# dram2.net
KiCad netlist of a schematic drawn in Altium Designer
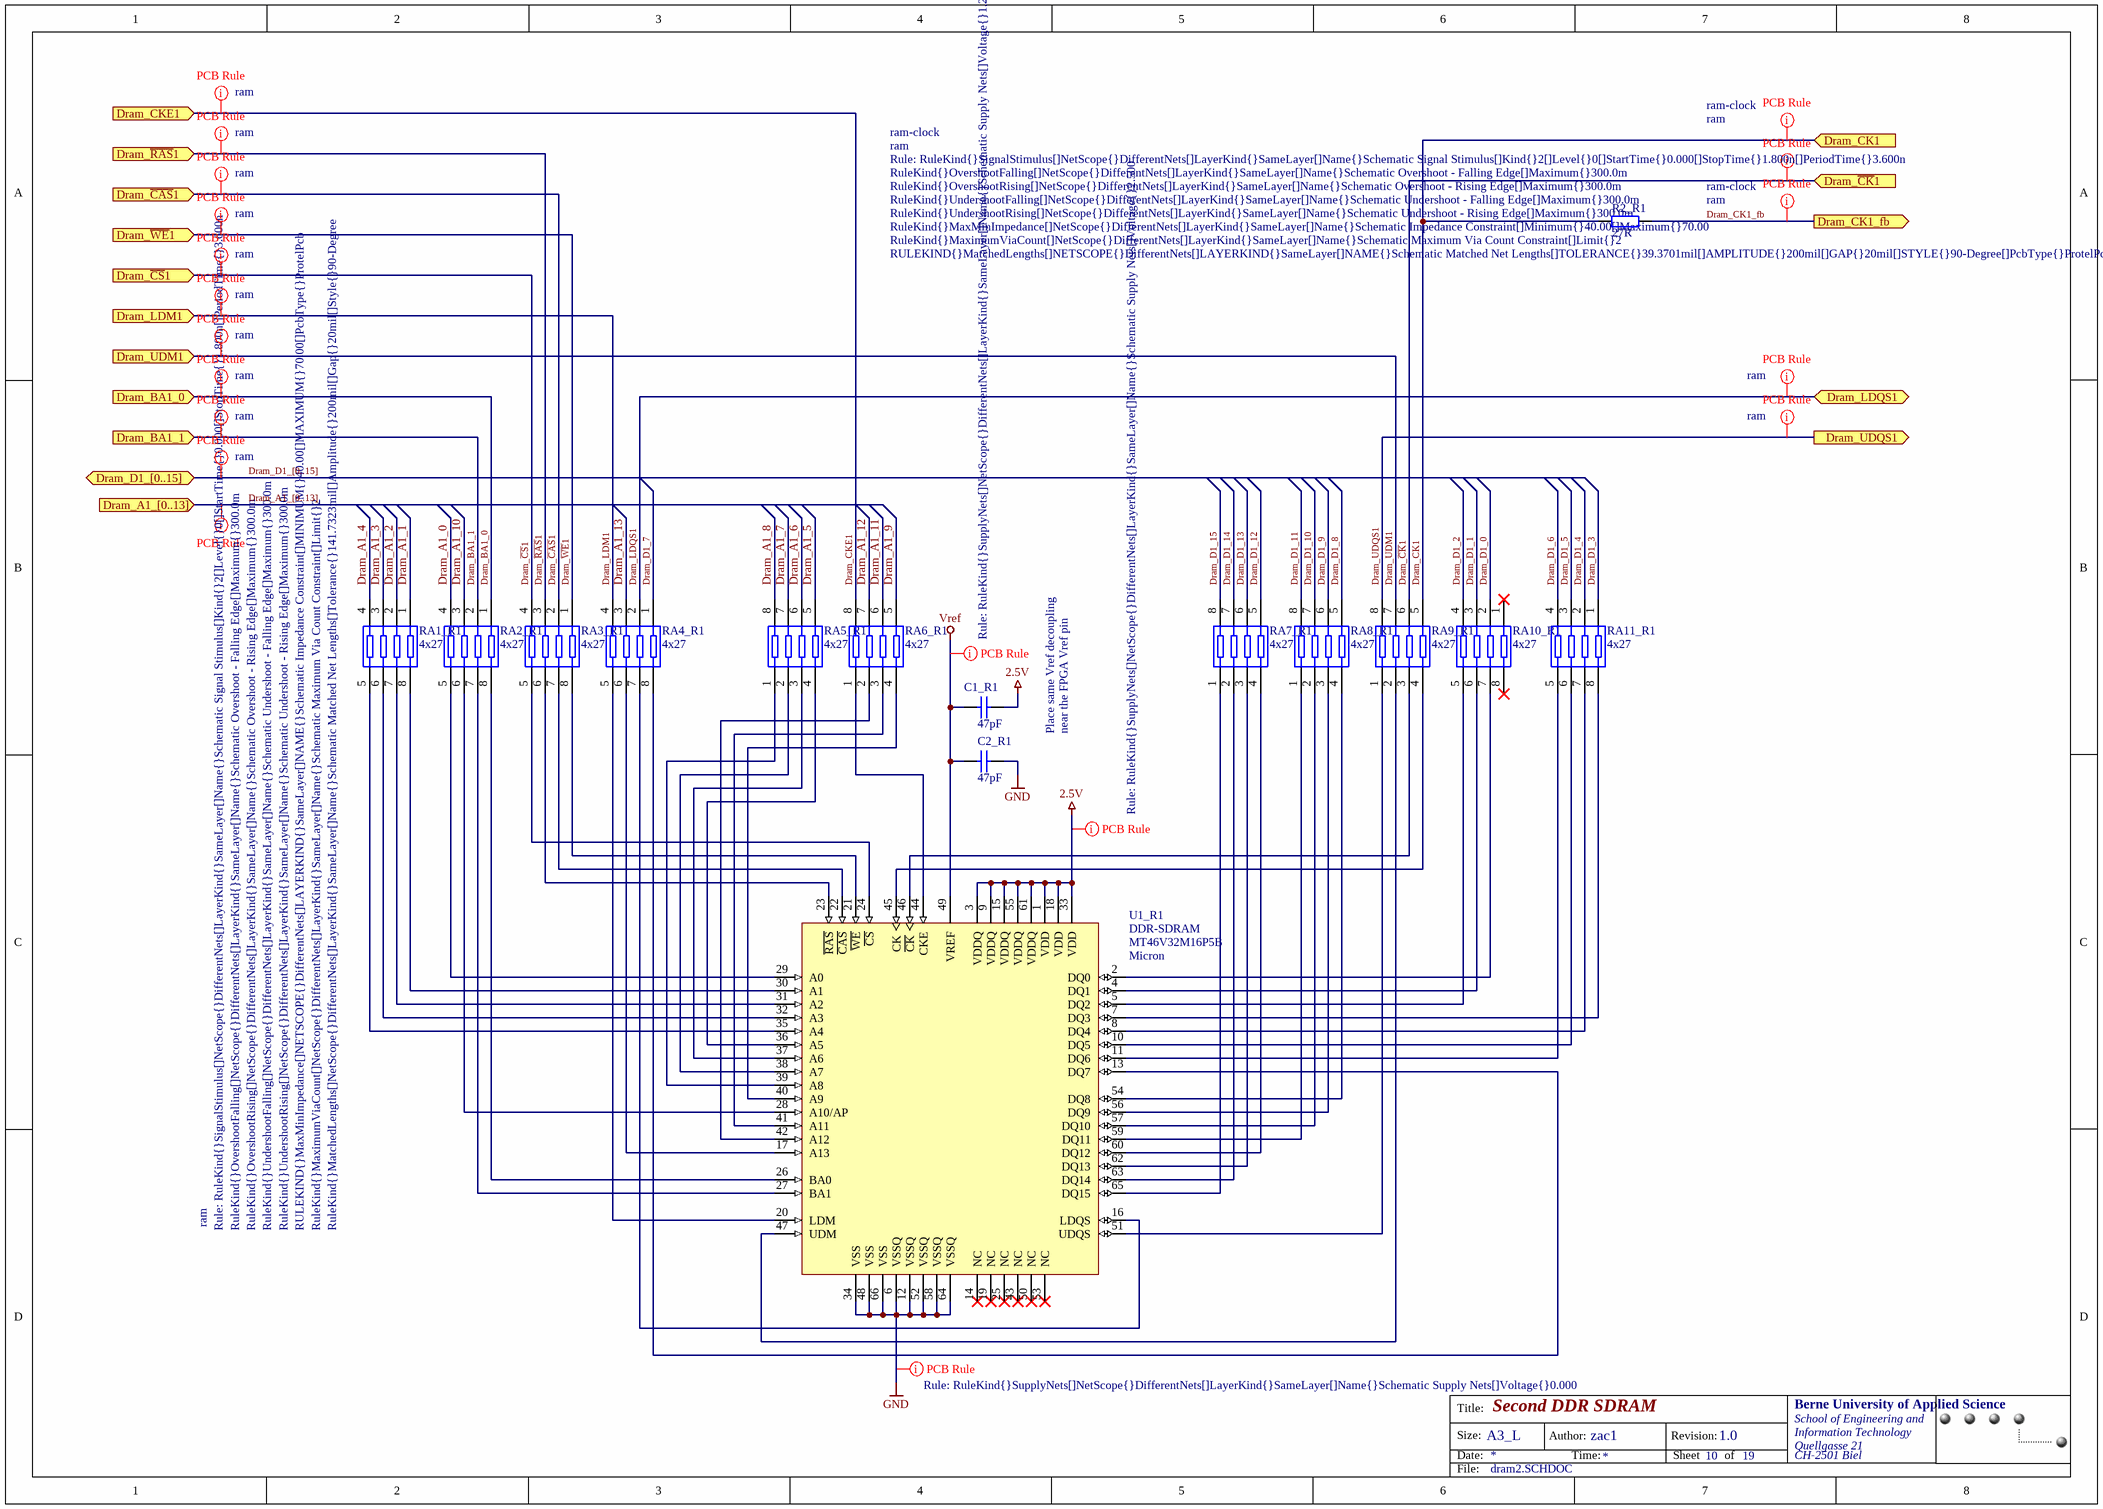
[diagram p0: dram2.SCHDOC]

(export (version "E")
  (design (tool "Eeschema 10.0.6"))
  (components
    (comp (ref "C1_R1")
      (value "47pF")
      (footprint "0402")
      (description "Capacitor")
      (fields
        (field (name "MANUFACTURER") "Murata")
        (field (name "PART NUMBER") "GRM1555C1H470JZ01D")
        (field (name "PUBLISHER") "Altium Limited")
      )
      (libsource (lib "Miscellaneous Devices") (part "Cap"))
    )
    (comp (ref "C2_R1")
      (value "47pF")
      (footprint "0402")
      (description "Capacitor")
      (fields
        (field (name "MANUFACTURER") "Murata")
        (field (name "PART NUMBER") "GRM1555C1H470JZ01D")
        (field (name "PUBLISHER") "Altium Limited")
      )
      (libsource (lib "Miscellaneous Devices") (part "Cap"))
    )
    (comp (ref "R2_R1")
      (value "27R")
      (footprint "0402")
      (description "Resistor")
      (fields
        (field (name "MANUFACTURER") "PHYCOMP")
        (field (name "PART NUMBER") "232270672709")
        (field (name "PUBLISHER") "Altium Limited")
      )
      (libsource (lib "Miscellaneous Devices") (part "Res2"))
    )
    (comp (ref "RA1_R1")
      (value "4x27")
      (footprint "1206_ARRAY")
      (fields (field (name "MANUFACTURER") "PHYCOMP") (field (name "PART NUMBER") "235003410279"))
      (libsource (lib "CoolARM-Kit") (part "R_ARRAY_4_SMD"))
    )
    (comp (ref "RA2_R1")
      (value "4x27")
      (footprint "1206_ARRAY")
      (fields (field (name "MANUFACTURER") "PHYCOMP") (field (name "PART NUMBER") "235003410279"))
      (libsource (lib "CoolARM-Kit") (part "R_ARRAY_4_SMD"))
    )
    (comp (ref "RA3_R1")
      (value "4x27")
      (footprint "1206_ARRAY")
      (fields (field (name "MANUFACTURER") "PHYCOMP") (field (name "PART NUMBER") "235003410279"))
      (libsource (lib "CoolARM-Kit") (part "R_ARRAY_4_SMD"))
    )
    (comp (ref "RA4_R1")
      (value "4x27")
      (footprint "1206_ARRAY")
      (fields (field (name "MANUFACTURER") "PHYCOMP") (field (name "PART NUMBER") "235003410279"))
      (libsource (lib "CoolARM-Kit") (part "R_ARRAY_4_SMD"))
    )
    (comp (ref "RA5_R1")
      (value "4x27")
      (footprint "1206_ARRAY")
      (fields (field (name "MANUFACTURER") "PHYCOMP") (field (name "PART NUMBER") "235003410279"))
      (libsource (lib "CoolARM-Kit") (part "R_ARRAY_4_SMD"))
    )
    (comp (ref "RA6_R1")
      (value "4x27")
      (footprint "1206_ARRAY")
      (fields (field (name "MANUFACTURER") "PHYCOMP") (field (name "PART NUMBER") "235003410279"))
      (libsource (lib "CoolARM-Kit") (part "R_ARRAY_4_SMD"))
    )
    (comp (ref "RA7_R1")
      (value "4x27")
      (footprint "1206_ARRAY")
      (fields (field (name "MANUFACTURER") "PHYCOMP") (field (name "PART NUMBER") "235003410279"))
      (libsource (lib "CoolARM-Kit") (part "R_ARRAY_4_SMD"))
    )
    (comp (ref "RA8_R1")
      (value "4x27")
      (footprint "1206_ARRAY")
      (fields (field (name "MANUFACTURER") "PHYCOMP") (field (name "PART NUMBER") "235003410279"))
      (libsource (lib "CoolARM-Kit") (part "R_ARRAY_4_SMD"))
    )
    (comp (ref "RA9_R1")
      (value "4x27")
      (footprint "1206_ARRAY")
      (fields (field (name "MANUFACTURER") "PHYCOMP") (field (name "PART NUMBER") "235003410279"))
      (libsource (lib "CoolARM-Kit") (part "R_ARRAY_4_SMD"))
    )
    (comp (ref "RA10_R1")
      (value "4x27")
      (footprint "1206_ARRAY")
      (fields (field (name "MANUFACTURER") "PHYCOMP") (field (name "PART NUMBER") "235003410279"))
      (libsource (lib "CoolARM-Kit") (part "R_ARRAY_4_SMD"))
    )
    (comp (ref "RA11_R1")
      (value "4x27")
      (footprint "1206_ARRAY")
      (fields (field (name "MANUFACTURER") "PHYCOMP") (field (name "PART NUMBER") "235003410279"))
      (libsource (lib "CoolARM-Kit") (part "R_ARRAY_4_SMD"))
    )
    (comp (ref "U1_R1")
      (value "DDR-SDRAM")
      (footprint "TSOP66")
      (description "general model for ddr sdram's")
      (fields
        (field (name "ALTIUM_VALUE") "MT46V32M16P5B")
        (field (name "VENDOR") "Micron")
        (field (name "MANUFACTURER") "Micron")
        (field (name "PART NUMBER") "MT46V32M16P5B")
      )
      (libsource (lib "gecko3-user") (part "DDR-SDRAM"))
    )
  )
  (nets
    (net (code "1") (name "/Dram_A1_0") (class "Default")
      (node (ref "RA2_R1") (pin "4") (pinfunction "4_4") (pintype "passive"))
    )
    (net (code "2") (name "/Dram_A1_1") (class "Default")
      (node (ref "RA1_R1") (pin "1") (pinfunction "1_1") (pintype "passive"))
    )
    (net (code "3") (name "/Dram_A1_2") (class "Default")
      (node (ref "RA1_R1") (pin "2") (pinfunction "2_2") (pintype "passive"))
    )
    (net (code "4") (name "/Dram_A1_3") (class "Default")
      (node (ref "RA1_R1") (pin "3") (pinfunction "3_3") (pintype "passive"))
    )
    (net (code "5") (name "/Dram_A1_4") (class "Default")
      (node (ref "RA1_R1") (pin "4") (pinfunction "4_4") (pintype "passive"))
    )
    (net (code "6") (name "/Dram_A1_5") (class "Default")
      (node (ref "RA5_R1") (pin "5") (pinfunction "5_5") (pintype "passive"))
    )
    (net (code "7") (name "/Dram_A1_6") (class "Default")
      (node (ref "RA5_R1") (pin "6") (pinfunction "6_6") (pintype "passive"))
    )
    (net (code "8") (name "/Dram_A1_7") (class "Default")
      (node (ref "RA5_R1") (pin "7") (pinfunction "7_7") (pintype "passive"))
    )
    (net (code "9") (name "/Dram_A1_8") (class "Default")
      (node (ref "RA5_R1") (pin "8") (pinfunction "8_8") (pintype "passive"))
    )
    (net (code "10") (name "/Dram_A1_9") (class "Default")
      (node (ref "RA6_R1") (pin "5") (pinfunction "5_5") (pintype "passive"))
    )
    (net (code "11") (name "/Dram_A1_10") (class "Default")
      (node (ref "RA2_R1") (pin "3") (pinfunction "3_3") (pintype "passive"))
    )
    (net (code "12") (name "/Dram_A1_11") (class "Default")
      (node (ref "RA6_R1") (pin "6") (pinfunction "6_6") (pintype "passive"))
    )
    (net (code "13") (name "/Dram_A1_12") (class "Default")
      (node (ref "RA6_R1") (pin "7") (pinfunction "7_7") (pintype "passive"))
    )
    (net (code "14") (name "/Dram_A1_13") (class "Default")
      (node (ref "RA4_R1") (pin "3") (pinfunction "3_3") (pintype "passive"))
    )
    (net (code "16") (name "/Dram_BA1_0") (class "Default")
      (node (ref "RA2_R1") (pin "1") (pinfunction "1_1") (pintype "passive"))
    )
    (net (code "17") (name "/Dram_BA1_1") (class "Default")
      (node (ref "RA2_R1") (pin "2") (pinfunction "2_2") (pintype "passive"))
    )
    (net (code "18") (name "/Dram_CK1") (class "Default")
      (node (ref "R2_R1") (pin "2") (pinfunction "2_2") (pintype "passive"))
      (node (ref "RA9_R1") (pin "5") (pinfunction "5_5") (pintype "passive"))
    )
    (net (code "19") (name "/Dram_CK1_fb") (class "Default")
      (node (ref "R2_R1") (pin "1") (pinfunction "1_1") (pintype "passive"))
    )
    (net (code "20") (name "/Dram_CKE1") (class "Default")
      (node (ref "RA6_R1") (pin "8") (pinfunction "8_8") (pintype "passive"))
    )
    (net (code "21") (name "/Dram_D1_0") (class "Default")
      (node (ref "RA10_R1") (pin "2") (pinfunction "2_2") (pintype "passive"))
    )
    (net (code "22") (name "/Dram_D1_1") (class "Default")
      (node (ref "RA10_R1") (pin "3") (pinfunction "3_3") (pintype "passive"))
    )
    (net (code "23") (name "/Dram_D1_2") (class "Default")
      (node (ref "RA10_R1") (pin "4") (pinfunction "4_4") (pintype "passive"))
    )
    (net (code "24") (name "/Dram_D1_3") (class "Default")
      (node (ref "RA11_R1") (pin "1") (pinfunction "1_1") (pintype "passive"))
    )
    (net (code "25") (name "/Dram_D1_4") (class "Default")
      (node (ref "RA11_R1") (pin "2") (pinfunction "2_2") (pintype "passive"))
    )
    (net (code "26") (name "/Dram_D1_5") (class "Default")
      (node (ref "RA11_R1") (pin "3") (pinfunction "3_3") (pintype "passive"))
    )
    (net (code "27") (name "/Dram_D1_6") (class "Default")
      (node (ref "RA11_R1") (pin "4") (pinfunction "4_4") (pintype "passive"))
    )
    (net (code "28") (name "/Dram_D1_7") (class "Default")
      (node (ref "RA4_R1") (pin "1") (pinfunction "1_1") (pintype "passive"))
    )
    (net (code "29") (name "/Dram_D1_8") (class "Default")
      (node (ref "RA8_R1") (pin "5") (pinfunction "5_5") (pintype "passive"))
    )
    (net (code "30") (name "/Dram_D1_9") (class "Default")
      (node (ref "RA8_R1") (pin "6") (pinfunction "6_6") (pintype "passive"))
    )
    (net (code "31") (name "/Dram_D1_10") (class "Default")
      (node (ref "RA8_R1") (pin "7") (pinfunction "7_7") (pintype "passive"))
    )
    (net (code "32") (name "/Dram_D1_11") (class "Default")
      (node (ref "RA8_R1") (pin "8") (pinfunction "8_8") (pintype "passive"))
    )
    (net (code "33") (name "/Dram_D1_12") (class "Default")
      (node (ref "RA7_R1") (pin "5") (pinfunction "5_5") (pintype "passive"))
    )
    (net (code "34") (name "/Dram_D1_13") (class "Default")
      (node (ref "RA7_R1") (pin "6") (pinfunction "6_6") (pintype "passive"))
    )
    (net (code "35") (name "/Dram_D1_14") (class "Default")
      (node (ref "RA7_R1") (pin "7") (pinfunction "7_7") (pintype "passive"))
    )
    (net (code "36") (name "/Dram_D1_15") (class "Default")
      (node (ref "RA7_R1") (pin "8") (pinfunction "8_8") (pintype "passive"))
    )
    (net (code "38") (name "/Dram_LDM1") (class "Default")
      (node (ref "RA4_R1") (pin "4") (pinfunction "4_4") (pintype "passive"))
    )
    (net (code "39") (name "/Dram_LDQS1") (class "Default")
      (node (ref "RA4_R1") (pin "2") (pinfunction "2_2") (pintype "passive"))
    )
    (net (code "40") (name "/Dram_UDM1") (class "Default")
      (node (ref "RA9_R1") (pin "7") (pinfunction "7_7") (pintype "passive"))
    )
    (net (code "41") (name "/Dram_UDQS1") (class "Default")
      (node (ref "RA9_R1") (pin "8") (pinfunction "8_8") (pintype "passive"))
    )
    (net (code "42") (name "/Dram_~{CAS}1") (class "Default")
      (node (ref "RA3_R1") (pin "2") (pinfunction "2_2") (pintype "passive"))
    )
    (net (code "43") (name "/Dram_~{CK}1") (class "Default")
      (node (ref "RA9_R1") (pin "6") (pinfunction "6_6") (pintype "passive"))
    )
    (net (code "44") (name "/Dram_~{CS}1") (class "Default")
      (node (ref "RA3_R1") (pin "4") (pinfunction "4_4") (pintype "passive"))
    )
    (net (code "45") (name "/Dram_~{RAS}1") (class "Default")
      (node (ref "RA3_R1") (pin "3") (pinfunction "3_3") (pintype "passive"))
    )
    (net (code "46") (name "/Dram_~{WE}1") (class "Default")
      (node (ref "RA3_R1") (pin "1") (pinfunction "1_1") (pintype "passive"))
    )
    (net (code "47") (name "2.5V") (class "Default")
      (node (ref "C1_R1") (pin "1") (pinfunction "1_1") (pintype "passive"))
      (node (ref "U1_R1") (pin "1") (pinfunction "VDD_1") (pintype "power_in"))
      (node (ref "U1_R1") (pin "15") (pinfunction "VDDQ_15") (pintype "power_in"))
      (node (ref "U1_R1") (pin "18") (pinfunction "VDD_18") (pintype "power_in"))
      (node (ref "U1_R1") (pin "3") (pinfunction "VDDQ_3") (pintype "power_in"))
      (node (ref "U1_R1") (pin "33") (pinfunction "VDD_33") (pintype "power_in"))
      (node (ref "U1_R1") (pin "55") (pinfunction "VDDQ_55") (pintype "power_in"))
      (node (ref "U1_R1") (pin "61") (pinfunction "VDDQ_61") (pintype "power_in"))
      (node (ref "U1_R1") (pin "9") (pinfunction "VDDQ_9") (pintype "power_in"))
    )
    (net (code "48") (name "GND") (class "Default")
      (node (ref "C2_R1") (pin "1") (pinfunction "1_1") (pintype "passive"))
      (node (ref "U1_R1") (pin "12") (pinfunction "VSSQ_12") (pintype "power_in"))
      (node (ref "U1_R1") (pin "34") (pinfunction "VSS_34") (pintype "power_in"))
      (node (ref "U1_R1") (pin "48") (pinfunction "VSS_48") (pintype "power_in"))
      (node (ref "U1_R1") (pin "52") (pinfunction "VSSQ_52") (pintype "power_in"))
      (node (ref "U1_R1") (pin "58") (pinfunction "VSSQ_58") (pintype "power_in"))
      (node (ref "U1_R1") (pin "6") (pinfunction "VSSQ_6") (pintype "power_in"))
      (node (ref "U1_R1") (pin "64") (pinfunction "VSSQ_64") (pintype "power_in"))
      (node (ref "U1_R1") (pin "66") (pinfunction "VSS_66") (pintype "power_in"))
    )
    (net (code "49") (name "Net-(U1_R1-A0)") (class "Default")
      (node (ref "RA2_R1") (pin "5") (pinfunction "5_5") (pintype "passive"))
      (node (ref "U1_R1") (pin "29") (pinfunction "A0_29") (pintype "input"))
    )
    (net (code "50") (name "Net-(U1_R1-A1)") (class "Default")
      (node (ref "RA1_R1") (pin "8") (pinfunction "8_8") (pintype "passive"))
      (node (ref "U1_R1") (pin "30") (pinfunction "A1_30") (pintype "input"))
    )
    (net (code "51") (name "Net-(U1_R1-A2)") (class "Default")
      (node (ref "RA1_R1") (pin "7") (pinfunction "7_7") (pintype "passive"))
      (node (ref "U1_R1") (pin "31") (pinfunction "A2_31") (pintype "input"))
    )
    (net (code "52") (name "Net-(U1_R1-A3)") (class "Default")
      (node (ref "RA1_R1") (pin "6") (pinfunction "6_6") (pintype "passive"))
      (node (ref "U1_R1") (pin "32") (pinfunction "A3_32") (pintype "input"))
    )
    (net (code "53") (name "Net-(U1_R1-A4)") (class "Default")
      (node (ref "RA1_R1") (pin "5") (pinfunction "5_5") (pintype "passive"))
      (node (ref "U1_R1") (pin "35") (pinfunction "A4_35") (pintype "input"))
    )
    (net (code "54") (name "Net-(U1_R1-A5)") (class "Default")
      (node (ref "RA5_R1") (pin "4") (pinfunction "4_4") (pintype "passive"))
      (node (ref "U1_R1") (pin "36") (pinfunction "A5_36") (pintype "input"))
    )
    (net (code "55") (name "Net-(U1_R1-A6)") (class "Default")
      (node (ref "RA5_R1") (pin "3") (pinfunction "3_3") (pintype "passive"))
      (node (ref "U1_R1") (pin "37") (pinfunction "A6_37") (pintype "input"))
    )
    (net (code "56") (name "Net-(U1_R1-A7)") (class "Default")
      (node (ref "RA5_R1") (pin "2") (pinfunction "2_2") (pintype "passive"))
      (node (ref "U1_R1") (pin "38") (pinfunction "A7_38") (pintype "input"))
    )
    (net (code "57") (name "Net-(U1_R1-A8)") (class "Default")
      (node (ref "RA5_R1") (pin "1") (pinfunction "1_1") (pintype "passive"))
      (node (ref "U1_R1") (pin "39") (pinfunction "A8_39") (pintype "input"))
    )
    (net (code "58") (name "Net-(U1_R1-A9)") (class "Default")
      (node (ref "RA6_R1") (pin "4") (pinfunction "4_4") (pintype "passive"))
      (node (ref "U1_R1") (pin "40") (pinfunction "A9_40") (pintype "input"))
    )
    (net (code "59") (name "Net-(U1_R1-A10{slash}AP)") (class "Default")
      (node (ref "RA2_R1") (pin "6") (pinfunction "6_6") (pintype "passive"))
      (node (ref "U1_R1") (pin "28") (pinfunction "A10/AP_28") (pintype "input"))
    )
    (net (code "60") (name "Net-(U1_R1-A11)") (class "Default")
      (node (ref "RA6_R1") (pin "3") (pinfunction "3_3") (pintype "passive"))
      (node (ref "U1_R1") (pin "41") (pinfunction "A11_41") (pintype "input"))
    )
    (net (code "61") (name "Net-(U1_R1-A12)") (class "Default")
      (node (ref "RA6_R1") (pin "2") (pinfunction "2_2") (pintype "passive"))
      (node (ref "U1_R1") (pin "42") (pinfunction "A12_42") (pintype "input"))
    )
    (net (code "62") (name "Net-(U1_R1-A13)") (class "Default")
      (node (ref "RA4_R1") (pin "6") (pinfunction "6_6") (pintype "passive"))
      (node (ref "U1_R1") (pin "17") (pinfunction "A13_17") (pintype "input"))
    )
    (net (code "63") (name "Net-(U1_R1-BA0)") (class "Default")
      (node (ref "RA2_R1") (pin "8") (pinfunction "8_8") (pintype "passive"))
      (node (ref "U1_R1") (pin "26") (pinfunction "BA0_26") (pintype "input"))
    )
    (net (code "64") (name "Net-(U1_R1-BA1)") (class "Default")
      (node (ref "RA2_R1") (pin "7") (pinfunction "7_7") (pintype "passive"))
      (node (ref "U1_R1") (pin "27") (pinfunction "BA1_27") (pintype "input"))
    )
    (net (code "65") (name "Net-(U1_R1-CK)") (class "Default")
      (node (ref "RA9_R1") (pin "4") (pinfunction "4_4") (pintype "passive"))
      (node (ref "U1_R1") (pin "45") (pinfunction "CK_45") (pintype "input"))
    )
    (net (code "66") (name "Net-(U1_R1-CKE)") (class "Default")
      (node (ref "RA6_R1") (pin "1") (pinfunction "1_1") (pintype "passive"))
      (node (ref "U1_R1") (pin "44") (pinfunction "CKE_44") (pintype "input"))
    )
    (net (code "67") (name "Net-(U1_R1-DQ0)") (class "Default")
      (node (ref "RA10_R1") (pin "7") (pinfunction "7_7") (pintype "passive"))
      (node (ref "U1_R1") (pin "2") (pinfunction "DQ0_2") (pintype "bidirectional"))
    )
    (net (code "68") (name "Net-(U1_R1-DQ1)") (class "Default")
      (node (ref "RA10_R1") (pin "6") (pinfunction "6_6") (pintype "passive"))
      (node (ref "U1_R1") (pin "4") (pinfunction "DQ1_4") (pintype "bidirectional"))
    )
    (net (code "69") (name "Net-(U1_R1-DQ2)") (class "Default")
      (node (ref "RA10_R1") (pin "5") (pinfunction "5_5") (pintype "passive"))
      (node (ref "U1_R1") (pin "5") (pinfunction "DQ2_5") (pintype "bidirectional"))
    )
    (net (code "70") (name "Net-(U1_R1-DQ3)") (class "Default")
      (node (ref "RA11_R1") (pin "8") (pinfunction "8_8") (pintype "passive"))
      (node (ref "U1_R1") (pin "7") (pinfunction "DQ3_7") (pintype "bidirectional"))
    )
    (net (code "71") (name "Net-(U1_R1-DQ4)") (class "Default")
      (node (ref "RA11_R1") (pin "7") (pinfunction "7_7") (pintype "passive"))
      (node (ref "U1_R1") (pin "8") (pinfunction "DQ4_8") (pintype "bidirectional"))
    )
    (net (code "72") (name "Net-(U1_R1-DQ5)") (class "Default")
      (node (ref "RA11_R1") (pin "6") (pinfunction "6_6") (pintype "passive"))
      (node (ref "U1_R1") (pin "10") (pinfunction "DQ5_10") (pintype "bidirectional"))
    )
    (net (code "73") (name "Net-(U1_R1-DQ6)") (class "Default")
      (node (ref "RA11_R1") (pin "5") (pinfunction "5_5") (pintype "passive"))
      (node (ref "U1_R1") (pin "11") (pinfunction "DQ6_11") (pintype "bidirectional"))
    )
    (net (code "74") (name "Net-(U1_R1-DQ7)") (class "Default")
      (node (ref "RA4_R1") (pin "8") (pinfunction "8_8") (pintype "passive"))
      (node (ref "U1_R1") (pin "13") (pinfunction "DQ7_13") (pintype "bidirectional"))
    )
    (net (code "75") (name "Net-(U1_R1-DQ8)") (class "Default")
      (node (ref "RA8_R1") (pin "4") (pinfunction "4_4") (pintype "passive"))
      (node (ref "U1_R1") (pin "54") (pinfunction "DQ8_54") (pintype "bidirectional"))
    )
    (net (code "76") (name "Net-(U1_R1-DQ9)") (class "Default")
      (node (ref "RA8_R1") (pin "3") (pinfunction "3_3") (pintype "passive"))
      (node (ref "U1_R1") (pin "56") (pinfunction "DQ9_56") (pintype "bidirectional"))
    )
    (net (code "77") (name "Net-(U1_R1-DQ10)") (class "Default")
      (node (ref "RA8_R1") (pin "2") (pinfunction "2_2") (pintype "passive"))
      (node (ref "U1_R1") (pin "57") (pinfunction "DQ10_57") (pintype "bidirectional"))
    )
    (net (code "78") (name "Net-(U1_R1-DQ11)") (class "Default")
      (node (ref "RA8_R1") (pin "1") (pinfunction "1_1") (pintype "passive"))
      (node (ref "U1_R1") (pin "59") (pinfunction "DQ11_59") (pintype "bidirectional"))
    )
    (net (code "79") (name "Net-(U1_R1-DQ12)") (class "Default")
      (node (ref "RA7_R1") (pin "4") (pinfunction "4_4") (pintype "passive"))
      (node (ref "U1_R1") (pin "60") (pinfunction "DQ12_60") (pintype "bidirectional"))
    )
    (net (code "80") (name "Net-(U1_R1-DQ13)") (class "Default")
      (node (ref "RA7_R1") (pin "3") (pinfunction "3_3") (pintype "passive"))
      (node (ref "U1_R1") (pin "62") (pinfunction "DQ13_62") (pintype "bidirectional"))
    )
    (net (code "81") (name "Net-(U1_R1-DQ14)") (class "Default")
      (node (ref "RA7_R1") (pin "2") (pinfunction "2_2") (pintype "passive"))
      (node (ref "U1_R1") (pin "63") (pinfunction "DQ14_63") (pintype "bidirectional"))
    )
    (net (code "82") (name "Net-(U1_R1-DQ15)") (class "Default")
      (node (ref "RA7_R1") (pin "1") (pinfunction "1_1") (pintype "passive"))
      (node (ref "U1_R1") (pin "65") (pinfunction "DQ15_65") (pintype "bidirectional"))
    )
    (net (code "83") (name "Net-(U1_R1-LDM)") (class "Default")
      (node (ref "RA4_R1") (pin "5") (pinfunction "5_5") (pintype "passive"))
      (node (ref "U1_R1") (pin "20") (pinfunction "LDM_20") (pintype "input"))
    )
    (net (code "84") (name "Net-(U1_R1-LDQS)") (class "Default")
      (node (ref "RA4_R1") (pin "7") (pinfunction "7_7") (pintype "passive"))
      (node (ref "U1_R1") (pin "16") (pinfunction "LDQS_16") (pintype "bidirectional"))
    )
    (net (code "85") (name "Net-(U1_R1-UDM)") (class "Default")
      (node (ref "RA9_R1") (pin "2") (pinfunction "2_2") (pintype "passive"))
      (node (ref "U1_R1") (pin "47") (pinfunction "UDM_47") (pintype "input"))
    )
    (net (code "86") (name "Net-(U1_R1-UDQS)") (class "Default")
      (node (ref "RA9_R1") (pin "1") (pinfunction "1_1") (pintype "passive"))
      (node (ref "U1_R1") (pin "51") (pinfunction "UDQS_51") (pintype "bidirectional"))
    )
    (net (code "87") (name "Net-(U1_R1-~{CAS})") (class "Default")
      (node (ref "RA3_R1") (pin "7") (pinfunction "7_7") (pintype "passive"))
      (node (ref "U1_R1") (pin "22") (pinfunction "~{CAS}_22") (pintype "input"))
    )
    (net (code "88") (name "Net-(U1_R1-~{CK})") (class "Default")
      (node (ref "RA9_R1") (pin "3") (pinfunction "3_3") (pintype "passive"))
      (node (ref "U1_R1") (pin "46") (pinfunction "~{CK}_46") (pintype "input"))
    )
    (net (code "89") (name "Net-(U1_R1-~{CS})") (class "Default")
      (node (ref "RA3_R1") (pin "5") (pinfunction "5_5") (pintype "passive"))
      (node (ref "U1_R1") (pin "24") (pinfunction "~{CS}_24") (pintype "input"))
    )
    (net (code "90") (name "Net-(U1_R1-~{RAS})") (class "Default")
      (node (ref "RA3_R1") (pin "6") (pinfunction "6_6") (pintype "passive"))
      (node (ref "U1_R1") (pin "23") (pinfunction "~{RAS}_23") (pintype "input"))
    )
    (net (code "91") (name "Net-(U1_R1-~{WE})") (class "Default")
      (node (ref "RA3_R1") (pin "8") (pinfunction "8_8") (pintype "passive"))
      (node (ref "U1_R1") (pin "21") (pinfunction "~{WE}_21") (pintype "input"))
    )
    (net (code "92") (name "Vref") (class "Default")
      (node (ref "C1_R1") (pin "2") (pinfunction "2_2") (pintype "passive"))
      (node (ref "C2_R1") (pin "2") (pinfunction "2_2") (pintype "passive"))
      (node (ref "U1_R1") (pin "49") (pinfunction "VREF_49") (pintype "power_in"))
    )
    (net (code "93") (name "unconnected-(RA10_R1-Pad1)") (class "Default")
      (node (ref "RA10_R1") (pin "1") (pinfunction "1_1") (pintype "passive+no_connect"))
    )
    (net (code "94") (name "unconnected-(RA10_R1-Pad8)") (class "Default")
      (node (ref "RA10_R1") (pin "8") (pinfunction "8_8") (pintype "passive+no_connect"))
    )
    (net (code "95") (name "unconnected-(U1_R1-NC-Pad14)") (class "Default")
      (node (ref "U1_R1") (pin "14") (pinfunction "NC_14") (pintype "passive+no_connect"))
    )
    (net (code "96") (name "unconnected-(U1_R1-NC-Pad19)") (class "Default")
      (node (ref "U1_R1") (pin "19") (pinfunction "NC_19") (pintype "passive+no_connect"))
    )
    (net (code "97") (name "unconnected-(U1_R1-NC-Pad25)") (class "Default")
      (node (ref "U1_R1") (pin "25") (pinfunction "NC_25") (pintype "passive+no_connect"))
    )
    (net (code "98") (name "unconnected-(U1_R1-NC-Pad43)") (class "Default")
      (node (ref "U1_R1") (pin "43") (pinfunction "NC_43") (pintype "passive+no_connect"))
    )
    (net (code "99") (name "unconnected-(U1_R1-NC-Pad50)") (class "Default")
      (node (ref "U1_R1") (pin "50") (pinfunction "NC_50") (pintype "passive+no_connect"))
    )
    (net (code "100") (name "unconnected-(U1_R1-NC-Pad53)") (class "Default")
      (node (ref "U1_R1") (pin "53") (pinfunction "NC_53") (pintype "passive+no_connect"))
    )
  )
)
